# cs301_4---------------.net
KiCad netlist of a schematic drawn in Altium Designer
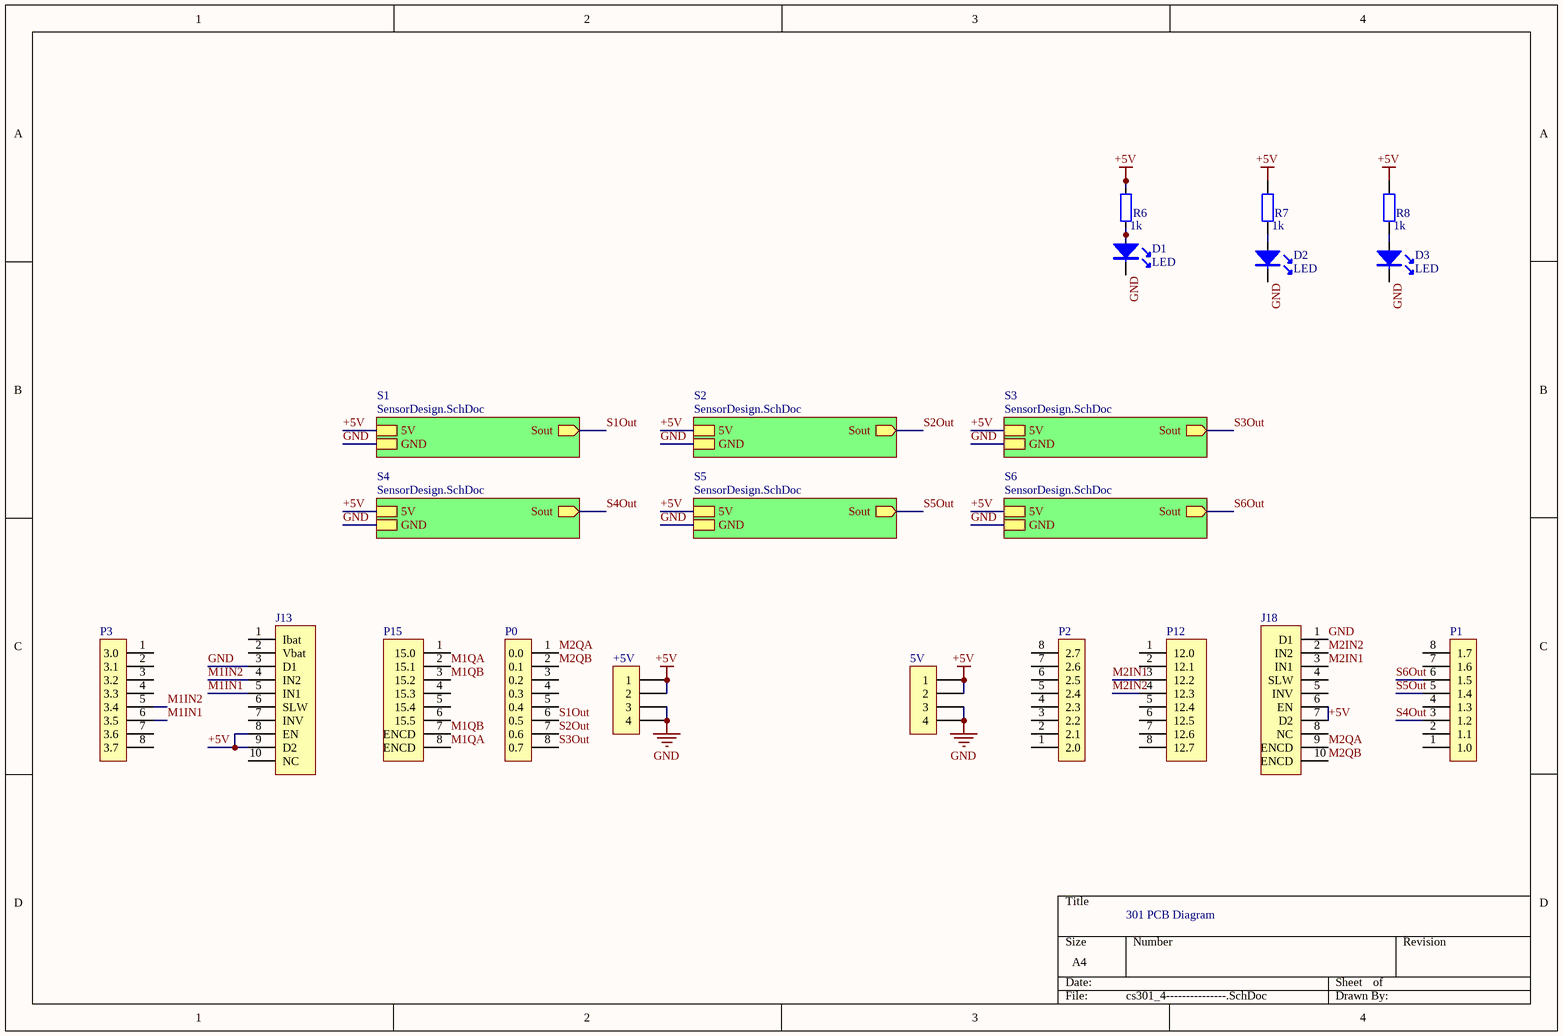
[diagram p0: cs301_4---------------.SchDoc]

(export (version "E")
  (design (tool "Eeschema 10.0.6"))
  (components
    (comp (ref "+5V")
      (value "5V")
      (footprint "IDC4")
      (description "Connector")
      (libsource (lib "Miscellaneous Devices") (part "CON4"))
    )
    (comp (ref "5V")
      (value "5V")
      (footprint "IDC4")
      (description "Connector")
      (libsource (lib "Miscellaneous Devices") (part "CON4"))
    )
    (comp (ref "D1") (value "LED") (footprint "LED0.1/5MM") (libsource (lib "COMSYS301") (part "LED")))
    (comp (ref "D2") (value "LED") (footprint "LED0.1/5MM") (libsource (lib "COMSYS301") (part "LED")))
    (comp (ref "D3") (value "LED") (footprint "LED0.1/5MM") (libsource (lib "COMSYS301") (part "LED")))
    (comp (ref "J13")
      (value "CON10")
      (footprint "idc10")
      (description "Connector")
      (libsource (lib "") (part "CON10_1"))
    )
    (comp (ref "J18")
      (value "CON10")
      (footprint "IDC10")
      (description "Connector")
      (libsource (lib "Miscellaneous Devices") (part "CON10"))
    )
    (comp (ref "P0")
      (value "P0")
      (footprint "idc8")
      (description "Connector")
      (libsource (lib "Miscellaneous Devices") (part "CON8"))
    )
    (comp (ref "P1")
      (value "P1")
      (footprint "idc8")
      (description "Connector")
      (libsource (lib "") (part "CON8_2"))
    )
    (comp (ref "P2")
      (value "P2")
      (footprint "idc8")
      (description "Connector")
      (libsource (lib "") (part "CON8_1"))
    )
    (comp (ref "P3")
      (value "P3")
      (footprint "idc8")
      (description "Connector")
      (libsource (lib "Miscellaneous Devices") (part "CON8"))
    )
    (comp (ref "P12")
      (value "P12")
      (footprint "idc8")
      (description "Connector")
      (libsource (lib "Miscellaneous Devices") (part "CON8_1"))
    )
    (comp (ref "P15")
      (value "P15")
      (footprint "idc8")
      (description "Connector")
      (libsource (lib "") (part "CON8_1_1"))
    )
    (comp (ref "R6")
      (value "1k")
      (footprint "0805 RES")
      (description "0805 resistor")
      (fields (field (name "PUBLISHER") "Altium Limited"))
      (libsource (lib "EE209_Library") (part "Res_SMT_0805"))
    )
    (comp (ref "R7")
      (value "1k")
      (footprint "0805 RES")
      (description "0805 resistor")
      (fields (field (name "PUBLISHER") "Altium Limited"))
      (libsource (lib "EE209_Library") (part "Res_SMT_0805"))
    )
    (comp (ref "R8")
      (value "1k")
      (footprint "0805 RES")
      (description "0805 resistor")
      (fields (field (name "PUBLISHER") "Altium Limited"))
      (libsource (lib "EE209_Library") (part "Res_SMT_0805"))
    )
  )
  (nets
    (net (code "1") (name "+5V") (class "Default")
      (node (ref "+5V") (pin "1") (pinfunction "1_1") (pintype "passive"))
      (node (ref "+5V") (pin "2") (pinfunction "2_2") (pintype "passive"))
      (node (ref "5V") (pin "1") (pinfunction "1_1") (pintype "passive"))
      (node (ref "5V") (pin "2") (pinfunction "2_2") (pintype "passive"))
      (node (ref "J13") (pin "8") (pinfunction "EN_8") (pintype "passive"))
      (node (ref "J13") (pin "9") (pinfunction "D2_9") (pintype "passive"))
      (node (ref "J18") (pin "6") (pinfunction "EN_6") (pintype "passive"))
      (node (ref "J18") (pin "7") (pinfunction "D2_7") (pintype "passive"))
      (node (ref "R6") (pin "1") (pinfunction "1_1") (pintype "passive"))
      (node (ref "R7") (pin "1") (pinfunction "1_1") (pintype "passive"))
      (node (ref "R8") (pin "1") (pinfunction "1_1") (pintype "passive"))
    )
    (net (code "2") (name "/M1IN1") (class "Default")
      (node (ref "J13") (pin "5") (pinfunction "IN1_5") (pintype "passive"))
      (node (ref "P3") (pin "6") (pinfunction "3.5_6") (pintype "passive"))
    )
    (net (code "3") (name "/M1IN2") (class "Default")
      (node (ref "J13") (pin "4") (pinfunction "IN2_4") (pintype "passive"))
      (node (ref "P3") (pin "5") (pinfunction "3.4_5") (pintype "passive"))
    )
    (net (code "4") (name "/M1QA") (class "Default")
      (node (ref "P15") (pin "2") (pinfunction "15.1_2") (pintype "passive"))
      (node (ref "P15") (pin "8") (pinfunction "ENCD_8") (pintype "passive"))
    )
    (net (code "5") (name "/M1QB") (class "Default")
      (node (ref "P15") (pin "3") (pinfunction "15.2_3") (pintype "passive"))
      (node (ref "P15") (pin "7") (pinfunction "ENCD_7") (pintype "passive"))
    )
    (net (code "6") (name "/M2IN1") (class "Default")
      (node (ref "J18") (pin "3") (pinfunction "IN1_3") (pintype "passive"))
      (node (ref "P12") (pin "3") (pinfunction "12.2_3") (pintype "passive"))
    )
    (net (code "7") (name "/M2IN2") (class "Default")
      (node (ref "J18") (pin "2") (pinfunction "IN2_2") (pintype "passive"))
      (node (ref "P12") (pin "4") (pinfunction "12.3_4") (pintype "passive"))
    )
    (net (code "8") (name "/M2QA") (class "Default")
      (node (ref "J18") (pin "9") (pinfunction "ENCD_9") (pintype "passive"))
      (node (ref "P0") (pin "1") (pinfunction "3.0_1") (pintype "passive"))
    )
    (net (code "9") (name "/M2QB") (class "Default")
      (node (ref "J18") (pin "10") (pinfunction "ENCD_10") (pintype "passive"))
      (node (ref "P0") (pin "2") (pinfunction "3.1_2") (pintype "passive"))
    )
    (net (code "10") (name "/S1Out") (class "Default")
      (node (ref "P0") (pin "6") (pinfunction "3.5_6") (pintype "passive"))
    )
    (net (code "11") (name "/S2Out") (class "Default")
      (node (ref "P0") (pin "7") (pinfunction "3.6_7") (pintype "passive"))
    )
    (net (code "12") (name "/S3Out") (class "Default")
      (node (ref "P0") (pin "8") (pinfunction "3.7_8") (pintype "passive"))
    )
    (net (code "13") (name "/S4Out") (class "Default")
      (node (ref "P1") (pin "3") (pinfunction "1.2_3") (pintype "passive"))
    )
    (net (code "14") (name "/S5Out") (class "Default")
      (node (ref "P1") (pin "5") (pinfunction "1.4_5") (pintype "passive"))
    )
    (net (code "15") (name "/S6Out") (class "Default")
      (node (ref "P1") (pin "6") (pinfunction "1.5_6") (pintype "passive"))
    )
    (net (code "16") (name "GND") (class "Default")
      (node (ref "+5V") (pin "3") (pinfunction "3_3") (pintype "passive"))
      (node (ref "+5V") (pin "4") (pinfunction "4_4") (pintype "passive"))
      (node (ref "5V") (pin "3") (pinfunction "3_3") (pintype "passive"))
      (node (ref "5V") (pin "4") (pinfunction "4_4") (pintype "passive"))
      (node (ref "D1") (pin "K") (pinfunction "2_K") (pintype "passive"))
      (node (ref "D2") (pin "K") (pinfunction "2_K") (pintype "passive"))
      (node (ref "D3") (pin "K") (pinfunction "2_K") (pintype "passive"))
      (node (ref "J13") (pin "3") (pinfunction "D1_3") (pintype "passive"))
      (node (ref "J18") (pin "1") (pinfunction "D1_1") (pintype "passive"))
    )
    (net (code "17") (name "Net-(D1-1)") (class "Default")
      (node (ref "D1") (pin "A") (pinfunction "1_A") (pintype "passive"))
      (node (ref "R6") (pin "2") (pinfunction "2_2") (pintype "passive"))
    )
    (net (code "18") (name "Net-(D2-1)") (class "Default")
      (node (ref "D2") (pin "A") (pinfunction "1_A") (pintype "passive"))
      (node (ref "R7") (pin "2") (pinfunction "2_2") (pintype "passive"))
    )
    (net (code "19") (name "Net-(D3-1)") (class "Default")
      (node (ref "D3") (pin "A") (pinfunction "1_A") (pintype "passive"))
      (node (ref "R8") (pin "2") (pinfunction "2_2") (pintype "passive"))
    )
    (net (code "20") (name "unconnected-(J13-INV-Pad7)") (class "Default")
      (node (ref "J13") (pin "7") (pinfunction "INV_7") (pintype "passive"))
    )
    (net (code "21") (name "unconnected-(J13-Ibat-Pad1)") (class "Default")
      (node (ref "J13") (pin "1") (pinfunction "Ibat_1") (pintype "passive"))
    )
    (net (code "22") (name "unconnected-(J13-NC-Pad10)") (class "Default")
      (node (ref "J13") (pin "10") (pinfunction "NC_10") (pintype "passive"))
    )
    (net (code "23") (name "unconnected-(J13-SLW-Pad6)") (class "Default")
      (node (ref "J13") (pin "6") (pinfunction "SLW_6") (pintype "passive"))
    )
    (net (code "24") (name "unconnected-(J13-Vbat-Pad2)") (class "Default")
      (node (ref "J13") (pin "2") (pinfunction "Vbat_2") (pintype "passive"))
    )
    (net (code "25") (name "unconnected-(J18-INV-Pad5)") (class "Default")
      (node (ref "J18") (pin "5") (pinfunction "INV_5") (pintype "passive"))
    )
    (net (code "26") (name "unconnected-(J18-NC-Pad8)") (class "Default")
      (node (ref "J18") (pin "8") (pinfunction "NC_8") (pintype "passive"))
    )
    (net (code "27") (name "unconnected-(J18-SLW-Pad4)") (class "Default")
      (node (ref "J18") (pin "4") (pinfunction "SLW_4") (pintype "passive"))
    )
    (net (code "28") (name "unconnected-(P0-3.2-Pad3)") (class "Default")
      (node (ref "P0") (pin "3") (pinfunction "3.2_3") (pintype "passive"))
    )
    (net (code "29") (name "unconnected-(P0-3.3-Pad4)") (class "Default")
      (node (ref "P0") (pin "4") (pinfunction "3.3_4") (pintype "passive"))
    )
    (net (code "30") (name "unconnected-(P0-3.4-Pad5)") (class "Default")
      (node (ref "P0") (pin "5") (pinfunction "3.4_5") (pintype "passive"))
    )
    (net (code "31") (name "unconnected-(P1-1.0-Pad1)") (class "Default")
      (node (ref "P1") (pin "1") (pinfunction "1.0_1") (pintype "passive"))
    )
    (net (code "32") (name "unconnected-(P1-1.1-Pad2)") (class "Default")
      (node (ref "P1") (pin "2") (pinfunction "1.1_2") (pintype "passive"))
    )
    (net (code "33") (name "unconnected-(P1-1.3-Pad4)") (class "Default")
      (node (ref "P1") (pin "4") (pinfunction "1.3_4") (pintype "passive"))
    )
    (net (code "34") (name "unconnected-(P1-1.6-Pad7)") (class "Default")
      (node (ref "P1") (pin "7") (pinfunction "1.6_7") (pintype "passive"))
    )
    (net (code "35") (name "unconnected-(P1-1.7-Pad8)") (class "Default")
      (node (ref "P1") (pin "8") (pinfunction "1.7_8") (pintype "passive"))
    )
    (net (code "36") (name "unconnected-(P2-2.0-Pad1)") (class "Default")
      (node (ref "P2") (pin "1") (pinfunction "2.0_1") (pintype "passive"))
    )
    (net (code "37") (name "unconnected-(P2-2.1-Pad2)") (class "Default")
      (node (ref "P2") (pin "2") (pinfunction "2.1_2") (pintype "passive"))
    )
    (net (code "38") (name "unconnected-(P2-2.2-Pad3)") (class "Default")
      (node (ref "P2") (pin "3") (pinfunction "2.2_3") (pintype "passive"))
    )
    (net (code "39") (name "unconnected-(P2-2.3-Pad4)") (class "Default")
      (node (ref "P2") (pin "4") (pinfunction "2.3_4") (pintype "passive"))
    )
    (net (code "40") (name "unconnected-(P2-2.4-Pad5)") (class "Default")
      (node (ref "P2") (pin "5") (pinfunction "2.4_5") (pintype "passive"))
    )
    (net (code "41") (name "unconnected-(P2-2.5-Pad6)") (class "Default")
      (node (ref "P2") (pin "6") (pinfunction "2.5_6") (pintype "passive"))
    )
    (net (code "42") (name "unconnected-(P2-2.6-Pad7)") (class "Default")
      (node (ref "P2") (pin "7") (pinfunction "2.6_7") (pintype "passive"))
    )
    (net (code "43") (name "unconnected-(P2-2.7-Pad8)") (class "Default")
      (node (ref "P2") (pin "8") (pinfunction "2.7_8") (pintype "passive"))
    )
    (net (code "44") (name "unconnected-(P3-3.0-Pad1)") (class "Default")
      (node (ref "P3") (pin "1") (pinfunction "3.0_1") (pintype "passive"))
    )
    (net (code "45") (name "unconnected-(P3-3.1-Pad2)") (class "Default")
      (node (ref "P3") (pin "2") (pinfunction "3.1_2") (pintype "passive"))
    )
    (net (code "46") (name "unconnected-(P3-3.2-Pad3)") (class "Default")
      (node (ref "P3") (pin "3") (pinfunction "3.2_3") (pintype "passive"))
    )
    (net (code "47") (name "unconnected-(P3-3.3-Pad4)") (class "Default")
      (node (ref "P3") (pin "4") (pinfunction "3.3_4") (pintype "passive"))
    )
    (net (code "48") (name "unconnected-(P3-3.6-Pad7)") (class "Default")
      (node (ref "P3") (pin "7") (pinfunction "3.6_7") (pintype "passive"))
    )
    (net (code "49") (name "unconnected-(P3-3.7-Pad8)") (class "Default")
      (node (ref "P3") (pin "8") (pinfunction "3.7_8") (pintype "passive"))
    )
    (net (code "50") (name "unconnected-(P12-12.0-Pad1)") (class "Default")
      (node (ref "P12") (pin "1") (pinfunction "12.0_1") (pintype "passive"))
    )
    (net (code "51") (name "unconnected-(P12-12.1-Pad2)") (class "Default")
      (node (ref "P12") (pin "2") (pinfunction "12.1_2") (pintype "passive"))
    )
    (net (code "52") (name "unconnected-(P12-12.4-Pad5)") (class "Default")
      (node (ref "P12") (pin "5") (pinfunction "12.4_5") (pintype "passive"))
    )
    (net (code "53") (name "unconnected-(P12-12.5-Pad6)") (class "Default")
      (node (ref "P12") (pin "6") (pinfunction "12.5_6") (pintype "passive"))
    )
    (net (code "54") (name "unconnected-(P12-12.6-Pad7)") (class "Default")
      (node (ref "P12") (pin "7") (pinfunction "12.6_7") (pintype "passive"))
    )
    (net (code "55") (name "unconnected-(P12-12.7-Pad8)") (class "Default")
      (node (ref "P12") (pin "8") (pinfunction "12.7_8") (pintype "passive"))
    )
    (net (code "56") (name "unconnected-(P15-15.0-Pad1)") (class "Default")
      (node (ref "P15") (pin "1") (pinfunction "15.0_1") (pintype "passive"))
    )
    (net (code "57") (name "unconnected-(P15-15.3-Pad4)") (class "Default")
      (node (ref "P15") (pin "4") (pinfunction "15.3_4") (pintype "passive"))
    )
    (net (code "58") (name "unconnected-(P15-15.4-Pad5)") (class "Default")
      (node (ref "P15") (pin "5") (pinfunction "15.4_5") (pintype "passive"))
    )
    (net (code "59") (name "unconnected-(P15-15.5-Pad6)") (class "Default")
      (node (ref "P15") (pin "6") (pinfunction "15.5_6") (pintype "passive"))
    )
  )
)
